# SparkFun_OpAmp_Breakout-LMV358.net
KiCad netlist of a schematic drawn in EAGLE
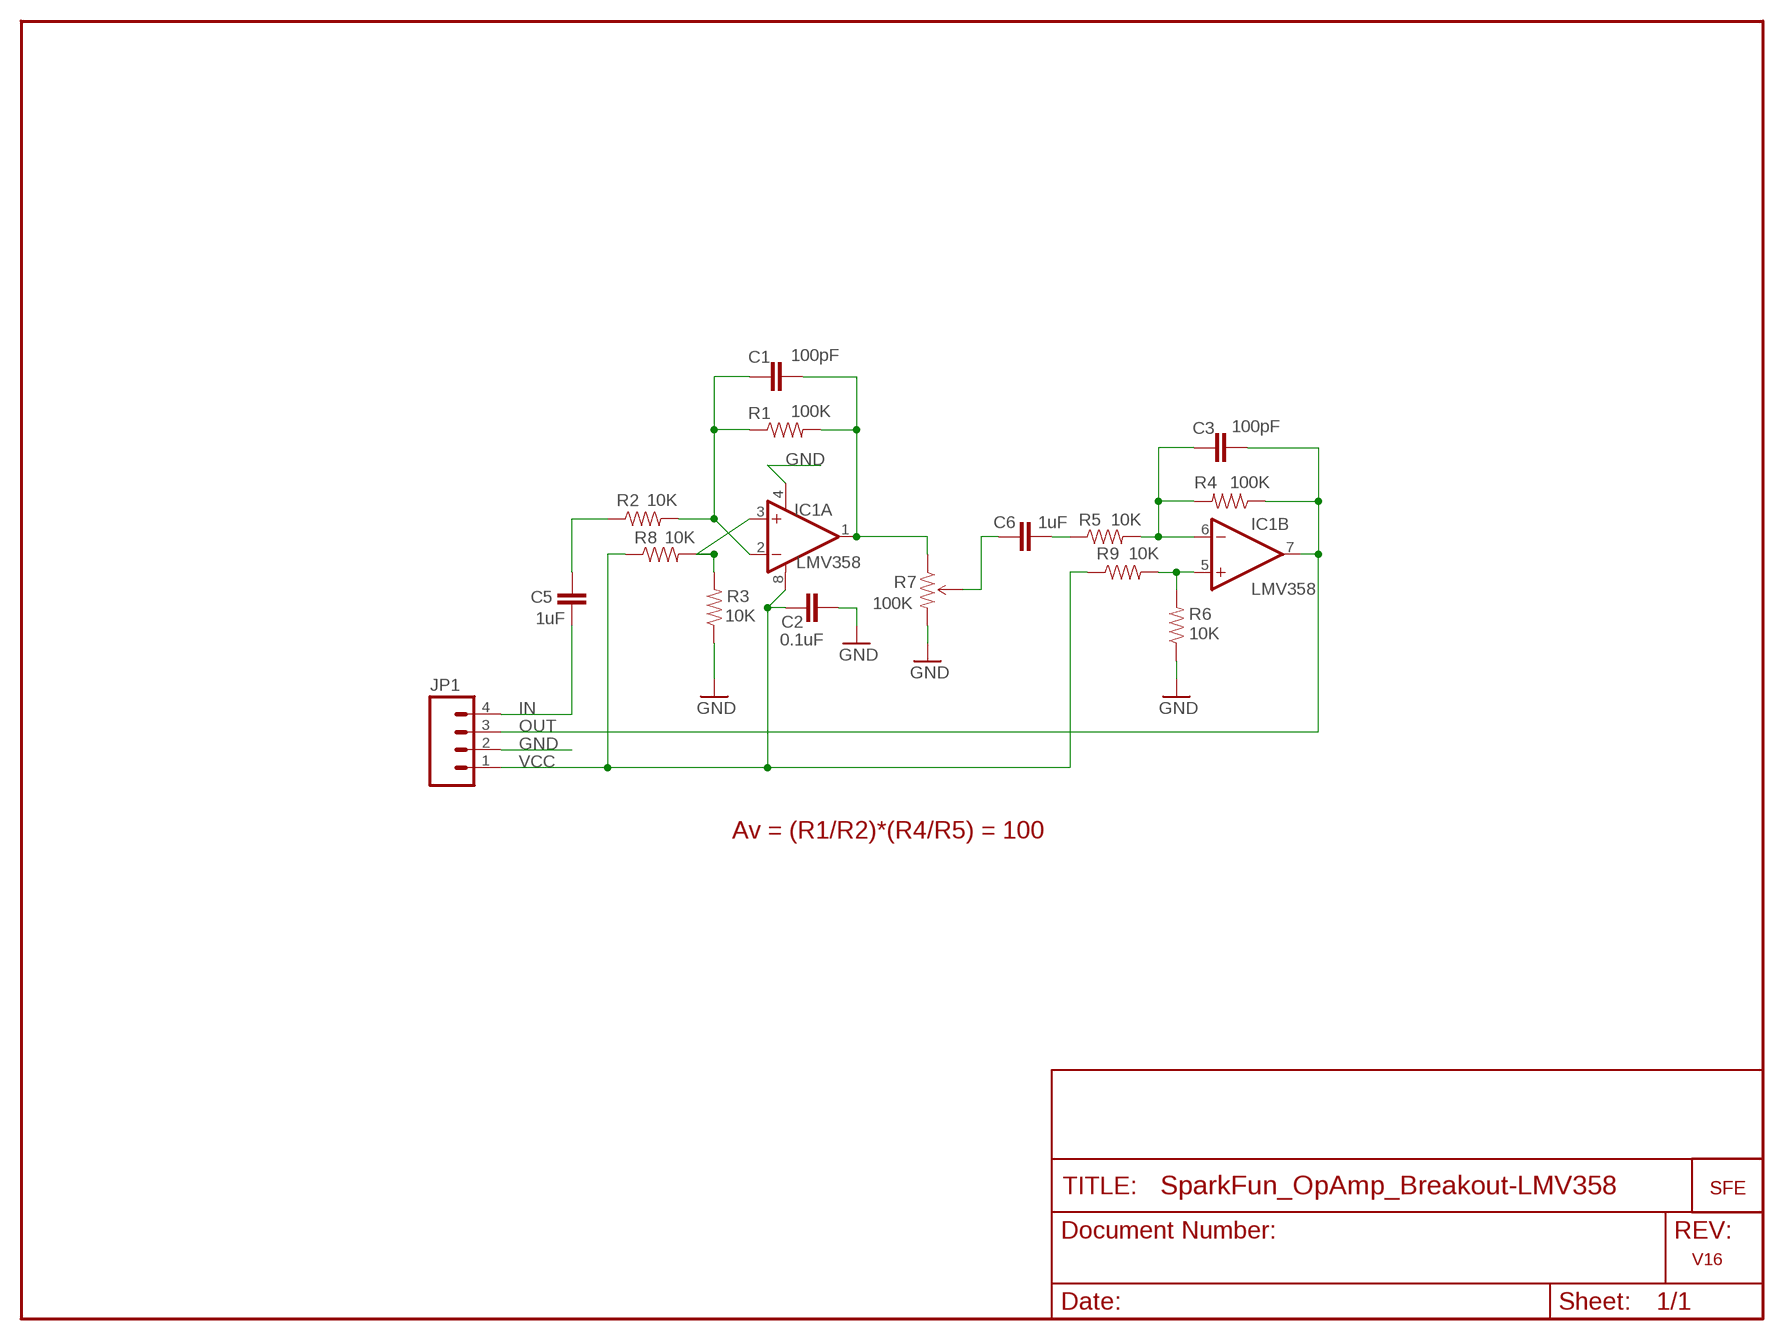
[diagram p0: schematic, sheet 1]

(export (version "E")
  (design (tool "Eeschema 10.0.6"))
  (components
    (comp (ref "C1")
      (value "100pF")
      (footprint "eagle-import:0402-CAP")
      (libsource (lib "eagle-import") (part "CAP0402-CAP"))
    )
    (comp (ref "C2")
      (value "0.1uF")
      (footprint "eagle-import:0402-CAP")
      (libsource (lib "eagle-import") (part "CAP0402-CAP"))
    )
    (comp (ref "C3")
      (value "100pF")
      (footprint "eagle-import:0402-CAP")
      (libsource (lib "eagle-import") (part "CAP0402-CAP"))
    )
    (comp (ref "C5")
      (value "1uF")
      (footprint "eagle-import:0402-CAP")
      (libsource (lib "eagle-import") (part "CAP0402-CAP"))
    )
    (comp (ref "C6")
      (value "1uF")
      (footprint "eagle-import:0402-CAP")
      (libsource (lib "eagle-import") (part "CAP0402-CAP"))
    )
    (comp (ref "IC1")
      (value "LMV358")
      (footprint "eagle-import:SO08")
      (libsource (lib "eagle-import") (part "OPAMP-DUALU"))
    )
    (comp (ref "JP1")
      (value "M04PTH")
      (footprint "eagle-import:1X04")
      (libsource (lib "eagle-import") (part "M04PTH"))
    )
    (comp (ref "R1")
      (value "100K")
      (footprint "eagle-import:0402-RES")
      (libsource (lib "eagle-import") (part "RESISTOR0402-RES"))
    )
    (comp (ref "R2")
      (value "10K")
      (footprint "eagle-import:0402-RES")
      (libsource (lib "eagle-import") (part "RESISTOR0402-RES"))
    )
    (comp (ref "R3")
      (value "10K")
      (footprint "eagle-import:0402-RES")
      (libsource (lib "eagle-import") (part "RESISTOR0402-RES"))
    )
    (comp (ref "R4")
      (value "100K")
      (footprint "eagle-import:0402-RES")
      (libsource (lib "eagle-import") (part "RESISTOR0402-RES"))
    )
    (comp (ref "R5")
      (value "10K")
      (footprint "eagle-import:0402-RES")
      (libsource (lib "eagle-import") (part "RESISTOR0402-RES"))
    )
    (comp (ref "R6")
      (value "10K")
      (footprint "eagle-import:0402-RES")
      (libsource (lib "eagle-import") (part "RESISTOR0402-RES"))
    )
    (comp (ref "R7")
      (value "100K")
      (footprint "eagle-import:TRIMPOT-3MM")
      (libsource (lib "eagle-import") (part "TRIMPOTSMD"))
    )
    (comp (ref "R8")
      (value "10K")
      (footprint "eagle-import:C0402")
      (libsource (lib "eagle-import") (part "RESISTOR0402"))
    )
    (comp (ref "R9")
      (value "10K")
      (footprint "eagle-import:C0402")
      (libsource (lib "eagle-import") (part "RESISTOR0402"))
    )
    (comp (ref "U$3")
      (value "LOGO-SFENEW")
      (footprint "eagle-import:SFE-NEW-WEBLOGO")
      (libsource (lib "eagle-import") (part "LOGO-SFENEW"))
    )
  )
  (nets
    (net (code "1") (name "/IN") (class "Default")
      (node (ref "C5") (pin "1") (pinfunction "1_1") (pintype "passive"))
      (node (ref "JP1") (pin "4") (pinfunction "4_4") (pintype "passive"))
    )
    (net (code "2") (name "/OUT") (class "Default")
      (node (ref "C3") (pin "2") (pinfunction "2_2") (pintype "passive"))
      (node (ref "IC1") (pin "7") (pinfunction "OUT_7") (pintype "output"))
      (node (ref "JP1") (pin "3") (pinfunction "3_3") (pintype "passive"))
      (node (ref "R4") (pin "1") (pinfunction "1_1") (pintype "passive"))
    )
    (net (code "3") (name "/VCC") (class "Default")
      (node (ref "C2") (pin "1") (pinfunction "1_1") (pintype "passive"))
      (node (ref "IC1") (pin "8") (pinfunction "V+_8") (pintype "power_in"))
      (node (ref "JP1") (pin "1") (pinfunction "1_1") (pintype "passive"))
      (node (ref "R8") (pin "1") (pinfunction "1_1") (pintype "passive"))
      (node (ref "R9") (pin "1") (pinfunction "1_1") (pintype "passive"))
    )
    (net (code "4") (name "GND") (class "Default")
      (node (ref "C2") (pin "2") (pinfunction "2_2") (pintype "passive"))
      (node (ref "IC1") (pin "4") (pinfunction "V-_4") (pintype "power_in"))
      (node (ref "JP1") (pin "2") (pinfunction "2_2") (pintype "passive"))
      (node (ref "R3") (pin "1") (pinfunction "1_1") (pintype "passive"))
      (node (ref "R6") (pin "1") (pinfunction "1_1") (pintype "passive"))
      (node (ref "R7") (pin "3") (pinfunction "CW_3") (pintype "passive"))
    )
    (net (code "5") (name "Net-(C5-Pad2)") (class "Default")
      (node (ref "C5") (pin "2") (pinfunction "2_2") (pintype "passive"))
      (node (ref "R2") (pin "1") (pinfunction "1_1") (pintype "passive"))
    )
    (net (code "6") (name "Net-(C6-Pad1)") (class "Default")
      (node (ref "C6") (pin "1") (pinfunction "1_1") (pintype "passive"))
      (node (ref "R5") (pin "1") (pinfunction "1_1") (pintype "passive"))
    )
    (net (code "7") (name "Net-(IC1A-+IN)") (class "Default")
      (node (ref "IC1") (pin "3") (pinfunction "+IN_3") (pintype "input"))
      (node (ref "R3") (pin "2") (pinfunction "2_2") (pintype "passive"))
      (node (ref "R8") (pin "2") (pinfunction "2_2") (pintype "passive"))
    )
    (net (code "8") (name "Net-(IC1A--IN)") (class "Default")
      (node (ref "C1") (pin "1") (pinfunction "1_1") (pintype "passive"))
      (node (ref "IC1") (pin "2") (pinfunction "-IN_2") (pintype "input"))
      (node (ref "R1") (pin "1") (pinfunction "1_1") (pintype "passive"))
      (node (ref "R2") (pin "2") (pinfunction "2_2") (pintype "passive"))
    )
    (net (code "9") (name "Net-(IC1A-OUT)") (class "Default")
      (node (ref "C1") (pin "2") (pinfunction "2_2") (pintype "passive"))
      (node (ref "IC1") (pin "1") (pinfunction "OUT_1") (pintype "output"))
      (node (ref "R1") (pin "2") (pinfunction "2_2") (pintype "passive"))
      (node (ref "R7") (pin "1") (pinfunction "CCW_1") (pintype "passive"))
    )
    (net (code "10") (name "Net-(IC1B-+IN)") (class "Default")
      (node (ref "IC1") (pin "5") (pinfunction "+IN_5") (pintype "input"))
      (node (ref "R6") (pin "2") (pinfunction "2_2") (pintype "passive"))
      (node (ref "R9") (pin "2") (pinfunction "2_2") (pintype "passive"))
    )
    (net (code "11") (name "Net-(IC1B--IN)") (class "Default")
      (node (ref "C3") (pin "1") (pinfunction "1_1") (pintype "passive"))
      (node (ref "IC1") (pin "6") (pinfunction "-IN_6") (pintype "input"))
      (node (ref "R4") (pin "2") (pinfunction "2_2") (pintype "passive"))
      (node (ref "R5") (pin "2") (pinfunction "2_2") (pintype "passive"))
    )
    (net (code "12") (name "Net-(R7-WIPER)") (class "Default")
      (node (ref "C6") (pin "2") (pinfunction "2_2") (pintype "passive"))
      (node (ref "R7") (pin "2") (pinfunction "WIPER_2") (pintype "passive"))
    )
  )
)
